# oresat-minusz-end-card.net
KiCad netlist of a schematic drawn in EAGLE
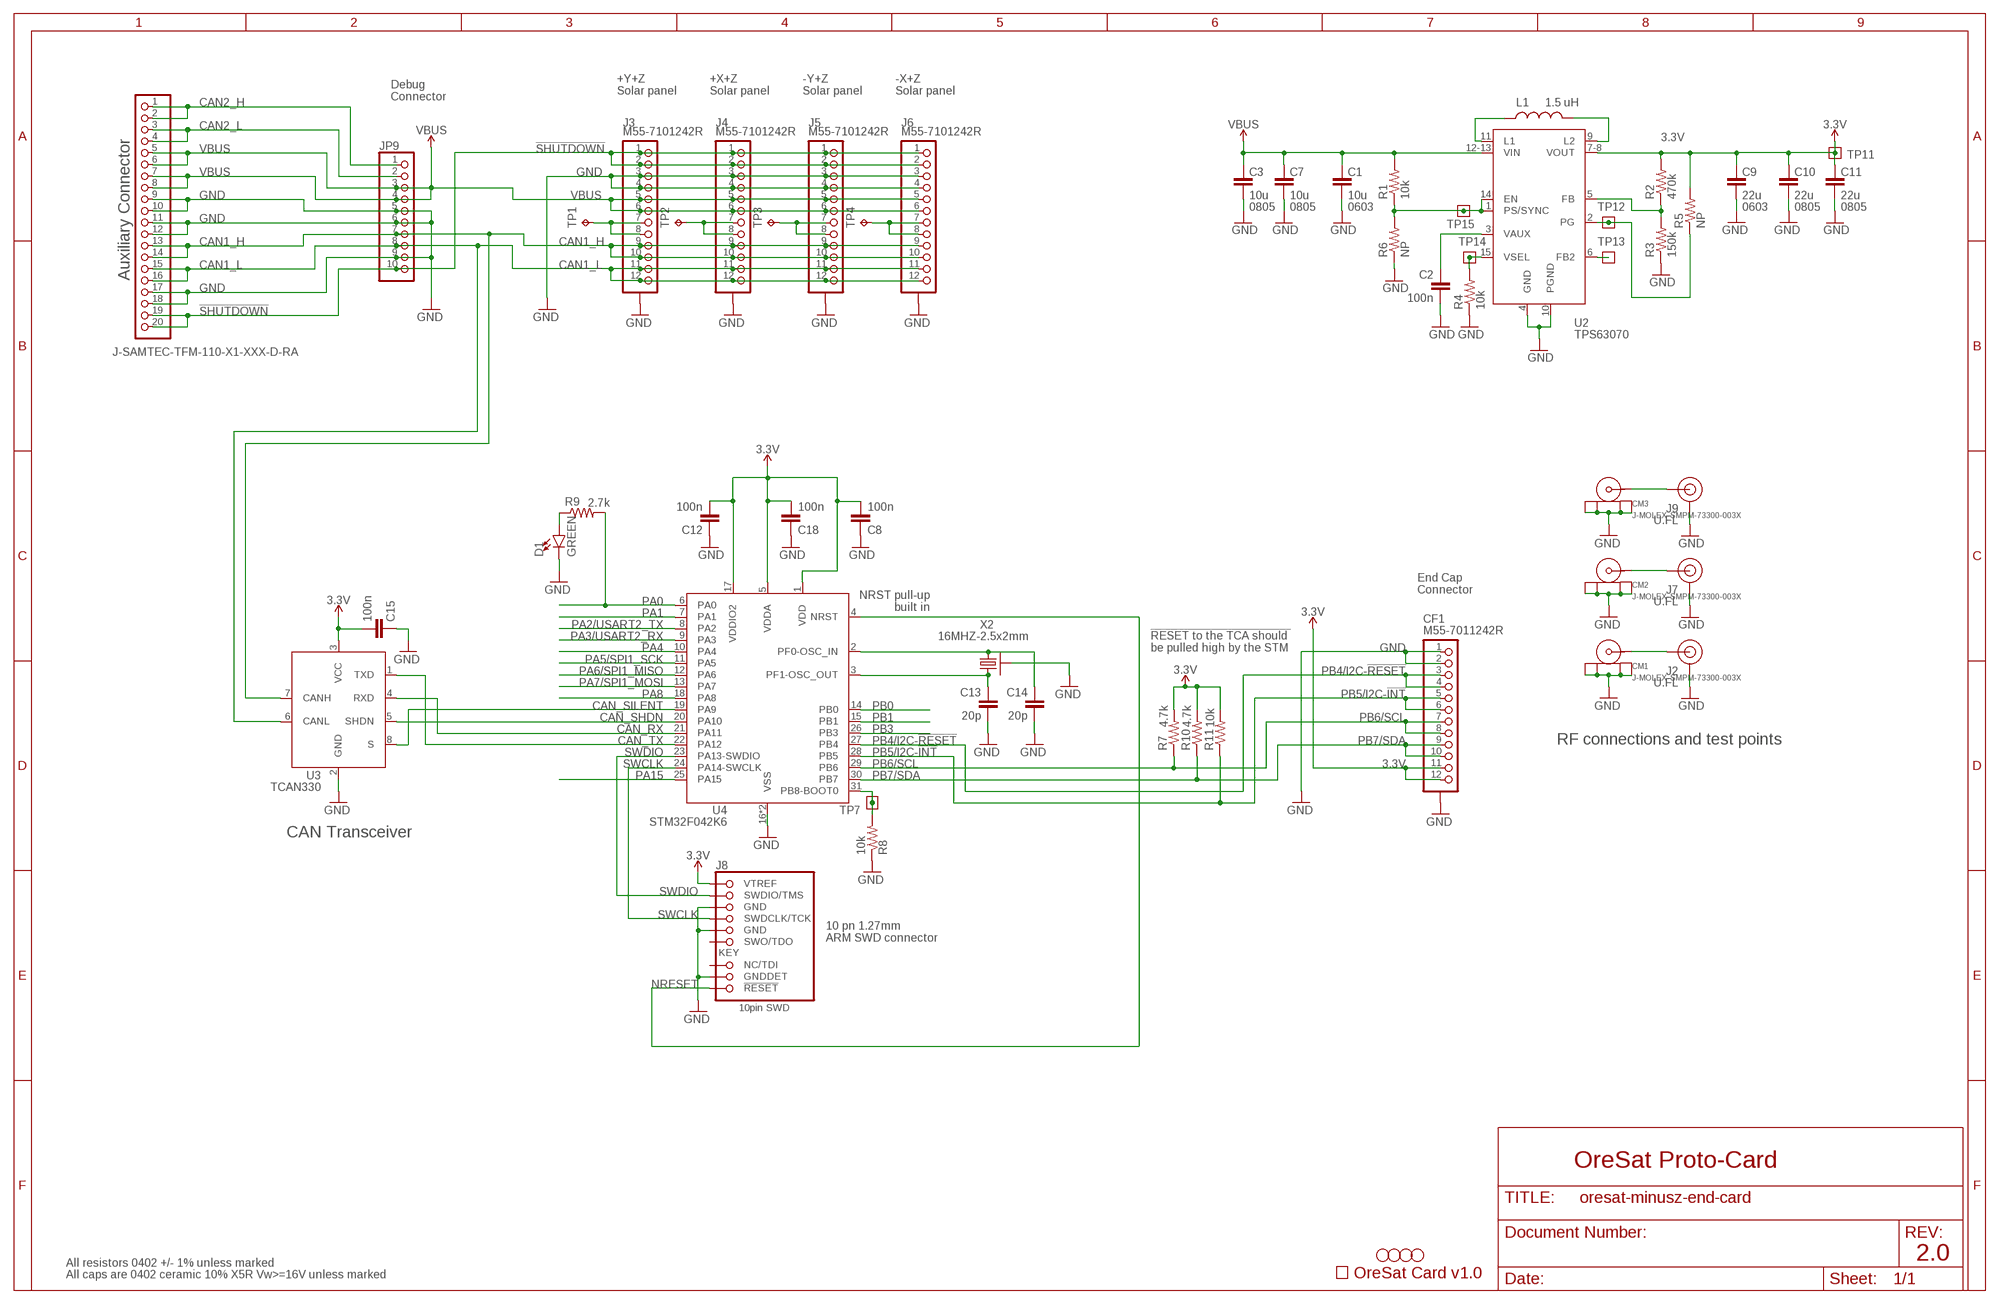
[diagram p0: schematic, sheet 1]

(export (version "E")
  (design (tool "Eeschema 10.0.6"))
  (components
    (comp (ref "C1")
      (value "10u")
      (footprint "eagle-import:.0603-B-NOSILK")
      (fields (field (name "MFR") "Samsung") (field (name "MPN") "CL05B104KO5NNNC"))
      (libsource (lib "eagle-import") (part "C-EU0603-B-NOSILK"))
    )
    (comp (ref "C2")
      (value "100n")
      (footprint "eagle-import:.0402-B-NOSILK")
      (fields (field (name "MFR") "Samsung") (field (name "MPN") "CL05B104KO5NNNC"))
      (libsource (lib "eagle-import") (part "rcl_custom_C-EU0402-B-NOSILK"))
    )
    (comp (ref "C3")
      (value "10u")
      (footprint "eagle-import:.0805-B-NOSILK")
      (libsource (lib "eagle-import") (part "C-EU0805-B-NOSILK"))
    )
    (comp (ref "C7")
      (value "10u")
      (footprint "eagle-import:.0805-B-NOSILK")
      (libsource (lib "eagle-import") (part "C-EU0805-B-NOSILK"))
    )
    (comp (ref "C8")
      (value "100n")
      (footprint "eagle-import:.0402-B-NOSILK")
      (fields (field (name "MFR") "Samsung") (field (name "MPN") "CL05B104KO5NNNC"))
      (libsource (lib "eagle-import") (part "rcl_custom_C-EU0402-B-NOSILK"))
    )
    (comp (ref "C9")
      (value "22u")
      (footprint "eagle-import:.0603-B-NOSILK")
      (fields (field (name "MFR") "Samsung") (field (name "MPN") "CL05B104KO5NNNC"))
      (libsource (lib "eagle-import") (part "C-EU0603-B-NOSILK"))
    )
    (comp (ref "C10")
      (value "22u")
      (footprint "eagle-import:.0805-B-NOSILK")
      (libsource (lib "eagle-import") (part "C-EU0805-B-NOSILK"))
    )
    (comp (ref "C11")
      (value "22u")
      (footprint "eagle-import:.0805-B-NOSILK")
      (libsource (lib "eagle-import") (part "C-EU0805-B-NOSILK"))
    )
    (comp (ref "C12")
      (value "100n")
      (footprint "eagle-import:.0402-B-NOSILK")
      (fields (field (name "MFR") "Samsung") (field (name "MPN") "CL05B104KO5NNNC"))
      (libsource (lib "eagle-import") (part "rcl_custom_C-EU0402-B-NOSILK"))
    )
    (comp (ref "C13")
      (value "20p")
      (footprint "eagle-import:.0402-B-NOSILK")
      (fields (field (name "MFR") "Samsung") (field (name "MPN") "CL05C200JB51PNC"))
      (libsource (lib "eagle-import") (part "rcl_custom_C-EU0402-B-NOSILK"))
    )
    (comp (ref "C14")
      (value "20p")
      (footprint "eagle-import:.0402-B-NOSILK")
      (fields (field (name "MFR") "Samsung") (field (name "MPN") "CL05C200JB51PNC"))
      (libsource (lib "eagle-import") (part "rcl_custom_C-EU0402-B-NOSILK"))
    )
    (comp (ref "C15")
      (value "100n")
      (footprint "eagle-import:.0402-B-NOSILK")
      (fields (field (name "MFR") "Samsung") (field (name "MPN") "CL05B104KO5NNNC"))
      (libsource (lib "eagle-import") (part "rcl_custom_C-EU0402-B-NOSILK"))
    )
    (comp (ref "C18")
      (value "100n")
      (footprint "eagle-import:.0402-B-NOSILK")
      (fields (field (name "MFR") "Samsung") (field (name "MPN") "CL05B104KO5NNNC"))
      (libsource (lib "eagle-import") (part "rcl_custom_C-EU0402-B-NOSILK"))
    )
    (comp (ref "CARD")
      (value "ORESAT-CARD-V0.5")
      (footprint "eagle-import:ORESAT-CARD-V1.0")
      (libsource (lib "eagle-import") (part "ORESAT-CARD-V0.5"))
    )
    (comp (ref "CF1")
      (value "M55-7011242R")
      (footprint "eagle-import:HARWIN-M55-6021242R")
      (libsource (lib "eagle-import") (part "J-HARWIN-M55-6021242R"))
    )
    (comp (ref "CM1")
      (value "J-MOLEX-SMPM-73300-003X")
      (footprint "eagle-import:J-MOLEX-SMPM-073300-003X")
      (libsource (lib "eagle-import") (part "J-MOLEX-SMPM-73300-003X"))
    )
    (comp (ref "CM2")
      (value "J-MOLEX-SMPM-73300-003X")
      (footprint "eagle-import:J-MOLEX-SMPM-073300-003X")
      (libsource (lib "eagle-import") (part "J-MOLEX-SMPM-73300-003X"))
    )
    (comp (ref "CM3")
      (value "J-MOLEX-SMPM-73300-003X")
      (footprint "eagle-import:J-MOLEX-SMPM-073300-003X")
      (libsource (lib "eagle-import") (part "J-MOLEX-SMPM-73300-003X"))
    )
    (comp (ref "D1")
      (value "GREEN")
      (footprint "eagle-import:LED-0603")
      (libsource (lib "eagle-import") (part "LED-GREEN0603"))
    )
    (comp (ref "H1")
      (value "STAND-OFFTIGHT")
      (footprint "eagle-import:STAND-OFF-TIGHT")
      (libsource (lib "eagle-import") (part "STAND-OFFTIGHT"))
    )
    (comp (ref "H2")
      (value "STAND-OFFTIGHT")
      (footprint "eagle-import:STAND-OFF-TIGHT")
      (libsource (lib "eagle-import") (part "STAND-OFFTIGHT"))
    )
    (comp (ref "H3")
      (value "STAND-OFFTIGHT")
      (footprint "eagle-import:STAND-OFF-TIGHT")
      (libsource (lib "eagle-import") (part "STAND-OFFTIGHT"))
    )
    (comp (ref "H4")
      (value "STAND-OFFTIGHT")
      (footprint "eagle-import:STAND-OFF-TIGHT")
      (libsource (lib "eagle-import") (part "STAND-OFFTIGHT"))
    )
    (comp (ref "J1")
      (value "J-SAMTEC-TFM-110-X1-XXX-D-RA")
      (footprint "eagle-import:J-SAMTEC-TFM-110-X1-XXX-D-RA")
      (fields (field (name "MFR") "Samtec") (field (name "MPN") "TFM-110-01-L-D-RA "))
      (libsource (lib "eagle-import") (part "J-SAMTEC-TFM-110-X1-XXX-D-RA"))
    )
    (comp (ref "J2")
      (value "U.FL")
      (footprint "eagle-import:U.FL")
      (libsource (lib "eagle-import") (part "U.FL2PIN"))
    )
    (comp (ref "J3")
      (value "M55-7101242R")
      (footprint "eagle-import:M55-7101242R")
      (libsource (lib "eagle-import") (part "M55-7101242R"))
    )
    (comp (ref "J4")
      (value "M55-7101242R")
      (footprint "eagle-import:M55-7101242R")
      (libsource (lib "eagle-import") (part "M55-7101242R"))
    )
    (comp (ref "J5")
      (value "M55-7101242R")
      (footprint "eagle-import:M55-7101242R")
      (libsource (lib "eagle-import") (part "M55-7101242R"))
    )
    (comp (ref "J6")
      (value "M55-7101242R")
      (footprint "eagle-import:M55-7101242R")
      (libsource (lib "eagle-import") (part "M55-7101242R"))
    )
    (comp (ref "J7")
      (value "U.FL")
      (footprint "eagle-import:U.FL")
      (libsource (lib "eagle-import") (part "U.FL2PIN"))
    )
    (comp (ref "J8")
      (value "FTSH-105-XX-X-DV-K")
      (footprint "eagle-import:CON10_2X5_DUK_FTSH")
      (fields (field (name "MFR") "CNC Tech") (field (name "MPN") "3220-10-0100-00"))
      (libsource (lib "eagle-import") (part "FTSH-105-XX-X-DV-K"))
    )
    (comp (ref "J9")
      (value "U.FL")
      (footprint "eagle-import:U.FL")
      (libsource (lib "eagle-import") (part "U.FL2PIN"))
    )
    (comp (ref "JP9")
      (value "PINHD-1X10")
      (footprint "eagle-import:1X10")
      (libsource (lib "eagle-import") (part "PINHD-1X10"))
    )
    (comp (ref "L1")
      (value "1.5 uH")
      (footprint "eagle-import:L-COILCRAFT-XFL4020")
      (fields (field (name "MFR") "Coilcraft") (field (name "MPN") "XFL4020-152ME"))
      (libsource (lib "eagle-import") (part "L-COILCRAFT-XFL4020"))
    )
    (comp (ref "R1")
      (value "10k")
      (footprint "eagle-import:.0402-B-NOSILK")
      (fields (field (name "MFR") "Samsung") (field (name "MPN") "RC1005F6653CS"))
      (libsource (lib "eagle-import") (part "R-US_0402-B-NOSILK"))
    )
    (comp (ref "R2")
      (value "470k")
      (footprint "eagle-import:.0402-B-NOSILK")
      (fields (field (name "MFR") "Samsung") (field (name "MPN") "RC1005F6653CS"))
      (libsource (lib "eagle-import") (part "R-US_0402-B-NOSILK"))
    )
    (comp (ref "R3")
      (value "150k")
      (footprint "eagle-import:.0402-B-NOSILK")
      (fields (field (name "MFR") "Samsung") (field (name "MPN") "RC1005F6653CS"))
      (libsource (lib "eagle-import") (part "R-US_0402-B-NOSILK"))
    )
    (comp (ref "R4")
      (value "10k")
      (footprint "eagle-import:.0402-B-NOSILK")
      (fields (field (name "MFR") "Samsung") (field (name "MPN") "RC1005F6653CS"))
      (libsource (lib "eagle-import") (part "R-US_0402-B-NOSILK"))
    )
    (comp (ref "R5")
      (value "NP")
      (footprint "eagle-import:.0402-B-NOSILK")
      (fields (field (name "MFR") "Samsung") (field (name "MPN") "RC1005F6653CS"))
      (libsource (lib "eagle-import") (part "R-US_0402-B-NOSILK"))
    )
    (comp (ref "R6")
      (value "NP")
      (footprint "eagle-import:.0402-B-NOSILK")
      (fields (field (name "MFR") "Samsung") (field (name "MPN") "RC1005F6653CS"))
      (libsource (lib "eagle-import") (part "R-US_0402-B-NOSILK"))
    )
    (comp (ref "R7")
      (value "4.7k")
      (footprint "eagle-import:.0402-B-NOSILK")
      (fields (field (name "MFR") "Samsung") (field (name "MPN") "RC1005F6653CS"))
      (libsource (lib "eagle-import") (part "R-US_0402-B-NOSILK"))
    )
    (comp (ref "R8")
      (value "10k")
      (footprint "eagle-import:.0402-B-NOSILK")
      (fields (field (name "MFR") "Samsung") (field (name "MPN") "RC1005F6653CS"))
      (libsource (lib "eagle-import") (part "R-US_0402-B-NOSILK"))
    )
    (comp (ref "R9")
      (value "2.7k")
      (footprint "eagle-import:.0402-B-NOSILK")
      (fields (field (name "MFR") "Samsung") (field (name "MPN") "RC1005F6653CS"))
      (libsource (lib "eagle-import") (part "R-US_0402-B-NOSILK"))
    )
    (comp (ref "R10")
      (value "4.7k")
      (footprint "eagle-import:.0402-B-NOSILK")
      (fields (field (name "MFR") "Samsung") (field (name "MPN") "RC1005F6653CS"))
      (libsource (lib "eagle-import") (part "R-US_0402-B-NOSILK"))
    )
    (comp (ref "R11")
      (value "10k")
      (footprint "eagle-import:.0402-B-NOSILK")
      (fields (field (name "MFR") "Samsung") (field (name "MPN") "RC1005F6653CS"))
      (libsource (lib "eagle-import") (part "R-US_0402-B-NOSILK"))
    )
    (comp (ref "TP1")
      (value "TPPAD1-13")
      (footprint "eagle-import:P1-13")
      (libsource (lib "eagle-import") (part "TPPAD1-13"))
    )
    (comp (ref "TP2")
      (value "TPPAD1-13")
      (footprint "eagle-import:P1-13")
      (libsource (lib "eagle-import") (part "TPPAD1-13"))
    )
    (comp (ref "TP3")
      (value "TPPAD1-13")
      (footprint "eagle-import:P1-13")
      (libsource (lib "eagle-import") (part "TPPAD1-13"))
    )
    (comp (ref "TP4")
      (value "TPPAD1-13")
      (footprint "eagle-import:P1-13")
      (libsource (lib "eagle-import") (part "TPPAD1-13"))
    )
    (comp (ref "TP7")
      (value "TEST-POINT")
      (footprint "eagle-import:2MM-TEST-POINT")
      (libsource (lib "eagle-import") (part "TEST-POINT"))
    )
    (comp (ref "TP11")
      (value "TEST-POINT")
      (footprint "eagle-import:2MM-TEST-POINT")
      (libsource (lib "eagle-import") (part "TEST-POINT"))
    )
    (comp (ref "TP12")
      (value "TEST-POINT")
      (footprint "eagle-import:2MM-TEST-POINT")
      (libsource (lib "eagle-import") (part "TEST-POINT"))
    )
    (comp (ref "TP13")
      (value "TEST-POINT")
      (footprint "eagle-import:2MM-TEST-POINT")
      (libsource (lib "eagle-import") (part "TEST-POINT"))
    )
    (comp (ref "TP14")
      (value "TEST-POINT")
      (footprint "eagle-import:2MM-TEST-POINT")
      (libsource (lib "eagle-import") (part "TEST-POINT"))
    )
    (comp (ref "TP15")
      (value "TEST-POINT")
      (footprint "eagle-import:2MM-TEST-POINT")
      (libsource (lib "eagle-import") (part "TEST-POINT"))
    )
    (comp (ref "U2")
      (value "TPS63070")
      (footprint "eagle-import:TPS63070X")
      (fields (field (name "MFR") "TI"))
      (libsource (lib "eagle-import") (part "TPS63070X"))
    )
    (comp (ref "U3")
      (value "TCAN330")
      (footprint "eagle-import:SOT23-8_TI-DCN")
      (fields (field (name "MFR") "Texas Instruments") (field (name "MPN") "TCAN330GDCNT"))
      (libsource (lib "eagle-import") (part "TCAN330"))
    )
    (comp (ref "U4")
      (value "STM32F042K6")
      (footprint "eagle-import:QFP32-7X7")
      (fields (field (name "MFR") "STMicroelectronics") (field (name "MPN") "STM32F042K6T7"))
      (libsource (lib "eagle-import") (part "STM32F042K6"))
    )
    (comp (ref "X2")
      (value "16MHZ-2.5x2mm")
      (footprint "eagle-import:CRYSTAL_2.5X2")
      (fields (field (name "MFR") "ECS Inc.") (field (name "MPN") "ECS-160-10-36Q-ES-TR"))
      (libsource (lib "eagle-import") (part "CRYSTAL-WITH-GND"))
    )
  )
  (nets
    (net (code "1") (name "/CAN1_H") (class "Default")
      (node (ref "J1") (pin "13") (pinfunction "13_13") (pintype "passive"))
      (node (ref "J1") (pin "14") (pinfunction "14_14") (pintype "passive"))
      (node (ref "J3") (pin "10") (pinfunction "10_10") (pintype "passive"))
      (node (ref "J3") (pin "9") (pinfunction "9_9") (pintype "passive"))
      (node (ref "J4") (pin "10") (pinfunction "10_10") (pintype "passive"))
      (node (ref "J4") (pin "9") (pinfunction "9_9") (pintype "passive"))
      (node (ref "J5") (pin "10") (pinfunction "10_10") (pintype "passive"))
      (node (ref "J5") (pin "9") (pinfunction "9_9") (pintype "passive"))
      (node (ref "J6") (pin "10") (pinfunction "10_10") (pintype "passive"))
      (node (ref "J6") (pin "9") (pinfunction "9_9") (pintype "passive"))
      (node (ref "JP9") (pin "7") (pinfunction "7_7") (pintype "passive"))
      (node (ref "U3") (pin "7") (pinfunction "CANH_7") (pintype "bidirectional"))
    )
    (net (code "2") (name "/CAN1_L") (class "Default")
      (node (ref "J1") (pin "15") (pinfunction "15_15") (pintype "passive"))
      (node (ref "J1") (pin "16") (pinfunction "16_16") (pintype "passive"))
      (node (ref "J3") (pin "11") (pinfunction "11_11") (pintype "passive"))
      (node (ref "J3") (pin "12") (pinfunction "12_12") (pintype "passive"))
      (node (ref "J4") (pin "11") (pinfunction "11_11") (pintype "passive"))
      (node (ref "J4") (pin "12") (pinfunction "12_12") (pintype "passive"))
      (node (ref "J5") (pin "11") (pinfunction "11_11") (pintype "passive"))
      (node (ref "J5") (pin "12") (pinfunction "12_12") (pintype "passive"))
      (node (ref "J6") (pin "11") (pinfunction "11_11") (pintype "passive"))
      (node (ref "J6") (pin "12") (pinfunction "12_12") (pintype "passive"))
      (node (ref "JP9") (pin "8") (pinfunction "8_8") (pintype "passive"))
      (node (ref "U3") (pin "6") (pinfunction "CANL_6") (pintype "bidirectional"))
    )
    (net (code "3") (name "/CAN2_H") (class "Default")
      (node (ref "J1") (pin "1") (pinfunction "1_1") (pintype "passive"))
      (node (ref "J1") (pin "2") (pinfunction "2_2") (pintype "passive"))
      (node (ref "JP9") (pin "1") (pinfunction "1_1") (pintype "passive"))
    )
    (net (code "4") (name "/CAN2_L") (class "Default")
      (node (ref "J1") (pin "3") (pinfunction "3_3") (pintype "passive"))
      (node (ref "J1") (pin "4") (pinfunction "4_4") (pintype "passive"))
      (node (ref "JP9") (pin "2") (pinfunction "2_2") (pintype "passive"))
    )
    (net (code "5") (name "/CAN_RX") (class "Default")
      (node (ref "U3") (pin "4") (pinfunction "RXD_4") (pintype "output"))
      (node (ref "U4") (pin "21") (pinfunction "PA11_21") (pintype "bidirectional"))
    )
    (net (code "6") (name "/CAN_SHDN") (class "Default")
      (node (ref "U3") (pin "5") (pinfunction "SHDN_5") (pintype "input"))
      (node (ref "U4") (pin "20") (pinfunction "PA10_20") (pintype "bidirectional"))
    )
    (net (code "7") (name "/CAN_SILENT") (class "Default")
      (node (ref "U3") (pin "8") (pinfunction "S_8") (pintype "input"))
      (node (ref "U4") (pin "19") (pinfunction "PA9_19") (pintype "bidirectional"))
    )
    (net (code "8") (name "/CAN_TX") (class "Default")
      (node (ref "U3") (pin "1") (pinfunction "TXD_1") (pintype "input"))
      (node (ref "U4") (pin "22") (pinfunction "PA12_22") (pintype "bidirectional"))
    )
    (net (code "9") (name "/NRESET") (class "Default")
      (node (ref "J8") (pin "10") (pinfunction "~{RESET}_10") (pintype "passive"))
      (node (ref "U4") (pin "4") (pinfunction "NRST_4") (pintype "bidirectional"))
    )
    (net (code "10") (name "/PA0") (class "Default")
      (node (ref "R9") (pin "2") (pinfunction "2_2") (pintype "passive"))
      (node (ref "U4") (pin "6") (pinfunction "PA0_6") (pintype "bidirectional"))
    )
    (net (code "11") (name "/PA1") (class "Default")
      (node (ref "U4") (pin "7") (pinfunction "PA1_7") (pintype "bidirectional"))
    )
    (net (code "12") (name "/PA2{slash}USART2_TX") (class "Default")
      (node (ref "U4") (pin "8") (pinfunction "PA2_8") (pintype "bidirectional"))
    )
    (net (code "13") (name "/PA3{slash}USART2_RX") (class "Default")
      (node (ref "U4") (pin "9") (pinfunction "PA3_9") (pintype "bidirectional"))
    )
    (net (code "14") (name "/PA4") (class "Default")
      (node (ref "U4") (pin "10") (pinfunction "PA4_10") (pintype "bidirectional"))
    )
    (net (code "15") (name "/PA5{slash}SPI1_SCK") (class "Default")
      (node (ref "U4") (pin "11") (pinfunction "PA5_11") (pintype "bidirectional"))
    )
    (net (code "16") (name "/PA6{slash}SPI1_MISO") (class "Default")
      (node (ref "U4") (pin "12") (pinfunction "PA6_12") (pintype "bidirectional"))
    )
    (net (code "17") (name "/PA7{slash}SPI1_MOSI") (class "Default")
      (node (ref "U4") (pin "13") (pinfunction "PA7_13") (pintype "bidirectional"))
    )
    (net (code "18") (name "/PA8") (class "Default")
      (node (ref "U4") (pin "18") (pinfunction "PA8_18") (pintype "bidirectional"))
    )
    (net (code "19") (name "/PA15") (class "Default")
      (node (ref "U4") (pin "25") (pinfunction "PA15_25") (pintype "bidirectional"))
    )
    (net (code "20") (name "/PB0") (class "Default")
      (node (ref "U4") (pin "14") (pinfunction "PB0_14") (pintype "bidirectional"))
    )
    (net (code "21") (name "/PB1") (class "Default")
      (node (ref "U4") (pin "15") (pinfunction "PB1_15") (pintype "bidirectional"))
    )
    (net (code "22") (name "/PB3") (class "Default")
      (node (ref "U4") (pin "26") (pinfunction "PB3_26") (pintype "bidirectional"))
    )
    (net (code "23") (name "/PB4{slash}I2C-~{RESET}") (class "Default")
      (node (ref "CF1") (pin "3") (pinfunction "3_3") (pintype "passive"))
      (node (ref "CF1") (pin "4") (pinfunction "4_4") (pintype "passive"))
      (node (ref "U4") (pin "27") (pinfunction "PB4_27") (pintype "bidirectional"))
    )
    (net (code "24") (name "/PB5{slash}I2C-~{INT}") (class "Default")
      (node (ref "CF1") (pin "5") (pinfunction "5_5") (pintype "passive"))
      (node (ref "CF1") (pin "6") (pinfunction "6_6") (pintype "passive"))
      (node (ref "R11") (pin "1") (pinfunction "1_1") (pintype "passive"))
      (node (ref "U4") (pin "28") (pinfunction "PB5_28") (pintype "bidirectional"))
    )
    (net (code "25") (name "/PB6{slash}SCL") (class "Default")
      (node (ref "CF1") (pin "7") (pinfunction "7_7") (pintype "passive"))
      (node (ref "CF1") (pin "8") (pinfunction "8_8") (pintype "passive"))
      (node (ref "R7") (pin "1") (pinfunction "1_1") (pintype "passive"))
      (node (ref "U4") (pin "29") (pinfunction "PB6_29") (pintype "bidirectional"))
    )
    (net (code "26") (name "/PB7{slash}SDA") (class "Default")
      (node (ref "CF1") (pin "10") (pinfunction "10_10") (pintype "passive"))
      (node (ref "CF1") (pin "9") (pinfunction "9_9") (pintype "passive"))
      (node (ref "R10") (pin "1") (pinfunction "1_1") (pintype "passive"))
      (node (ref "U4") (pin "30") (pinfunction "PB7_30") (pintype "bidirectional"))
    )
    (net (code "27") (name "/SWCLK") (class "Default")
      (node (ref "J8") (pin "4") (pinfunction "SWDCLK/TCK_4") (pintype "passive"))
      (node (ref "U4") (pin "24") (pinfunction "PA14-SWCLK_24") (pintype "bidirectional"))
    )
    (net (code "28") (name "/SWDIO") (class "Default")
      (node (ref "J8") (pin "2") (pinfunction "SWDIO/TMS_2") (pintype "passive"))
      (node (ref "U4") (pin "23") (pinfunction "PA13-SWDIO_23") (pintype "bidirectional"))
    )
    (net (code "29") (name "/~{SHUTDOWN}") (class "Default")
      (node (ref "J1") (pin "19") (pinfunction "19_19") (pintype "passive"))
      (node (ref "J1") (pin "20") (pinfunction "20_20") (pintype "passive"))
      (node (ref "J3") (pin "1") (pinfunction "1_1") (pintype "passive"))
      (node (ref "J3") (pin "2") (pinfunction "2_2") (pintype "passive"))
      (node (ref "J4") (pin "1") (pinfunction "1_1") (pintype "passive"))
      (node (ref "J4") (pin "2") (pinfunction "2_2") (pintype "passive"))
      (node (ref "J5") (pin "1") (pinfunction "1_1") (pintype "passive"))
      (node (ref "J5") (pin "2") (pinfunction "2_2") (pintype "passive"))
      (node (ref "J6") (pin "1") (pinfunction "1_1") (pintype "passive"))
      (node (ref "J6") (pin "2") (pinfunction "2_2") (pintype "passive"))
      (node (ref "JP9") (pin "10") (pinfunction "10_10") (pintype "passive"))
    )
    (net (code "30") (name "3.3V") (class "Default")
      (node (ref "C10") (pin "1") (pinfunction "1_1") (pintype "passive"))
      (node (ref "C11") (pin "1") (pinfunction "1_1") (pintype "passive"))
      (node (ref "C12") (pin "2") (pinfunction "2_2") (pintype "passive"))
      (node (ref "C15") (pin "2") (pinfunction "2_2") (pintype "passive"))
      (node (ref "C18") (pin "2") (pinfunction "2_2") (pintype "passive"))
      (node (ref "C8") (pin "2") (pinfunction "2_2") (pintype "passive"))
      (node (ref "C9") (pin "1") (pinfunction "1_1") (pintype "passive"))
      (node (ref "CF1") (pin "11") (pinfunction "11_11") (pintype "passive"))
      (node (ref "CF1") (pin "12") (pinfunction "12_12") (pintype "passive"))
      (node (ref "J8") (pin "1") (pinfunction "VTREF_1") (pintype "passive"))
      (node (ref "R10") (pin "2") (pinfunction "2_2") (pintype "passive"))
      (node (ref "R11") (pin "2") (pinfunction "2_2") (pintype "passive"))
      (node (ref "R2") (pin "2") (pinfunction "2_2") (pintype "passive"))
      (node (ref "R5") (pin "2") (pinfunction "2_2") (pintype "passive"))
      (node (ref "R7") (pin "2") (pinfunction "2_2") (pintype "passive"))
      (node (ref "TP11") (pin "1") (pinfunction "1_1") (pintype "passive"))
      (node (ref "U2") (pin "7-8") (pinfunction "VOUT_7-8") (pintype "power_in"))
      (node (ref "U3") (pin "3") (pinfunction "VCC_3") (pintype "power_in"))
      (node (ref "U4") (pin "1") (pinfunction "VDD_1") (pintype "power_in"))
      (node (ref "U4") (pin "17") (pinfunction "VDDIO2_17") (pintype "power_in"))
      (node (ref "U4") (pin "5") (pinfunction "VDDA_5") (pintype "power_in"))
    )
    (net (code "31") (name "GND") (class "Default")
      (node (ref "C1") (pin "2") (pinfunction "2_2") (pintype "passive"))
      (node (ref "C10") (pin "2") (pinfunction "2_2") (pintype "passive"))
      (node (ref "C11") (pin "2") (pinfunction "2_2") (pintype "passive"))
      (node (ref "C12") (pin "1") (pinfunction "1_1") (pintype "passive"))
      (node (ref "C13") (pin "2") (pinfunction "2_2") (pintype "passive"))
      (node (ref "C14") (pin "2") (pinfunction "2_2") (pintype "passive"))
      (node (ref "C15") (pin "1") (pinfunction "1_1") (pintype "passive"))
      (node (ref "C18") (pin "1") (pinfunction "1_1") (pintype "passive"))
      (node (ref "C2") (pin "2") (pinfunction "2_2") (pintype "passive"))
      (node (ref "C3") (pin "2") (pinfunction "2_2") (pintype "passive"))
      (node (ref "C7") (pin "2") (pinfunction "2_2") (pintype "passive"))
      (node (ref "C8") (pin "1") (pinfunction "1_1") (pintype "passive"))
      (node (ref "C9") (pin "2") (pinfunction "2_2") (pintype "passive"))
      (node (ref "CF1") (pin "1") (pinfunction "1_1") (pintype "passive"))
      (node (ref "CF1") (pin "2") (pinfunction "2_2") (pintype "passive"))
      (node (ref "CF1") (pin "P$1") (pinfunction "SHIELDS_P$1") (pintype "passive"))
      (node (ref "CF1") (pin "P$2") (pinfunction "SHIELDS_P$2") (pintype "passive"))
      (node (ref "CF1") (pin "P$3") (pinfunction "SHIELDS_P$3") (pintype "passive"))
      (node (ref "CF1") (pin "P$4") (pinfunction "SHIELDS_P$4") (pintype "passive"))
      (node (ref "CM1") (pin "P$1") (pinfunction "SHIELD3_P$1") (pintype "passive"))
      (node (ref "CM1") (pin "P$2") (pinfunction "SHIELD2_P$2") (pintype "passive"))
      (node (ref "CM1") (pin "P$3") (pinfunction "SHIELD1_P$3") (pintype "passive"))
      (node (ref "CM1") (pin "P$4") (pinfunction "SHIELD_P$4") (pintype "passive"))
      (node (ref "CM2") (pin "P$1") (pinfunction "SHIELD3_P$1") (pintype "passive"))
      (node (ref "CM2") (pin "P$2") (pinfunction "SHIELD2_P$2") (pintype "passive"))
      (node (ref "CM2") (pin "P$3") (pinfunction "SHIELD1_P$3") (pintype "passive"))
      (node (ref "CM2") (pin "P$4") (pinfunction "SHIELD_P$4") (pintype "passive"))
      (node (ref "CM3") (pin "P$1") (pinfunction "SHIELD3_P$1") (pintype "passive"))
      (node (ref "CM3") (pin "P$2") (pinfunction "SHIELD2_P$2") (pintype "passive"))
      (node (ref "CM3") (pin "P$3") (pinfunction "SHIELD1_P$3") (pintype "passive"))
      (node (ref "CM3") (pin "P$4") (pinfunction "SHIELD_P$4") (pintype "passive"))
      (node (ref "D1") (pin "C") (pinfunction "C_C") (pintype "passive"))
      (node (ref "J1") (pin "10") (pinfunction "10_10") (pintype "passive"))
      (node (ref "J1") (pin "11") (pinfunction "11_11") (pintype "passive"))
      (node (ref "J1") (pin "12") (pinfunction "12_12") (pintype "passive"))
      (node (ref "J1") (pin "17") (pinfunction "17_17") (pintype "passive"))
      (node (ref "J1") (pin "18") (pinfunction "18_18") (pintype "passive"))
      (node (ref "J1") (pin "9") (pinfunction "9_9") (pintype "passive"))
      (node (ref "J2") (pin "1") (pinfunction "GND_1") (pintype "bidirectional"))
      (node (ref "J2") (pin "2") (pinfunction "GND_2") (pintype "bidirectional"))
      (node (ref "J3") (pin "3") (pinfunction "3_3") (pintype "passive"))
      (node (ref "J3") (pin "4") (pinfunction "4_4") (pintype "passive"))
      (node (ref "J3") (pin "P$1") (pinfunction "SHIELD_P$1") (pintype "passive"))
      (node (ref "J3") (pin "P$2") (pinfunction "SHIELD_P$2") (pintype "passive"))
      (node (ref "J3") (pin "P$3") (pinfunction "SHIELD_P$3") (pintype "passive"))
      (node (ref "J3") (pin "P$4") (pinfunction "SHIELD_P$4") (pintype "passive"))
      (node (ref "J4") (pin "3") (pinfunction "3_3") (pintype "passive"))
      (node (ref "J4") (pin "4") (pinfunction "4_4") (pintype "passive"))
      (node (ref "J4") (pin "P$1") (pinfunction "SHIELD_P$1") (pintype "passive"))
      (node (ref "J4") (pin "P$2") (pinfunction "SHIELD_P$2") (pintype "passive"))
      (node (ref "J4") (pin "P$3") (pinfunction "SHIELD_P$3") (pintype "passive"))
      (node (ref "J4") (pin "P$4") (pinfunction "SHIELD_P$4") (pintype "passive"))
      (node (ref "J5") (pin "3") (pinfunction "3_3") (pintype "passive"))
      (node (ref "J5") (pin "4") (pinfunction "4_4") (pintype "passive"))
      (node (ref "J5") (pin "P$1") (pinfunction "SHIELD_P$1") (pintype "passive"))
      (node (ref "J5") (pin "P$2") (pinfunction "SHIELD_P$2") (pintype "passive"))
      (node (ref "J5") (pin "P$3") (pinfunction "SHIELD_P$3") (pintype "passive"))
      (node (ref "J5") (pin "P$4") (pinfunction "SHIELD_P$4") (pintype "passive"))
      (node (ref "J6") (pin "3") (pinfunction "3_3") (pintype "passive"))
      (node (ref "J6") (pin "4") (pinfunction "4_4") (pintype "passive"))
      (node (ref "J6") (pin "P$1") (pinfunction "SHIELD_P$1") (pintype "passive"))
      (node (ref "J6") (pin "P$2") (pinfunction "SHIELD_P$2") (pintype "passive"))
      (node (ref "J6") (pin "P$3") (pinfunction "SHIELD_P$3") (pintype "passive"))
      (node (ref "J6") (pin "P$4") (pinfunction "SHIELD_P$4") (pintype "passive"))
      (node (ref "J7") (pin "1") (pinfunction "GND_1") (pintype "bidirectional"))
      (node (ref "J7") (pin "2") (pinfunction "GND_2") (pintype "bidirectional"))
      (node (ref "J8") (pin "3") (pinfunction "GND_3") (pintype "passive"))
      (node (ref "J8") (pin "5") (pinfunction "GND_5") (pintype "passive"))
      (node (ref "J8") (pin "9") (pinfunction "GNDDET_9") (pintype "passive"))
      (node (ref "J9") (pin "1") (pinfunction "GND_1") (pintype "bidirectional"))
      (node (ref "J9") (pin "2") (pinfunction "GND_2") (pintype "bidirectional"))
      (node (ref "JP9") (pin "5") (pinfunction "5_5") (pintype "passive"))
      (node (ref "JP9") (pin "6") (pinfunction "6_6") (pintype "passive"))
      (node (ref "JP9") (pin "9") (pinfunction "9_9") (pintype "passive"))
      (node (ref "R3") (pin "1") (pinfunction "1_1") (pintype "passive"))
      (node (ref "R4") (pin "1") (pinfunction "1_1") (pintype "passive"))
      (node (ref "R6") (pin "1") (pinfunction "1_1") (pintype "passive"))
      (node (ref "R8") (pin "1") (pinfunction "1_1") (pintype "passive"))
      (node (ref "U2") (pin "10") (pinfunction "PGND_10") (pintype "power_in"))
      (node (ref "U2") (pin "4") (pinfunction "GND_4") (pintype "power_in"))
      (node (ref "U3") (pin "2") (pinfunction "GND_2") (pintype "power_in"))
      (node (ref "U4") (pin "16") (pinfunction "VSS_16") (pintype "power_in"))
      (node (ref "U4") (pin "32") (pinfunction "VSS_32") (pintype "power_in"))
      (node (ref "X2") (pin "2") (pinfunction "SHIELD_2") (pintype "power_in"))
      (node (ref "X2") (pin "4") (pinfunction "SHIELD_4") (pintype "power_in"))
    )
    (net (code "32") (name "Net-(CM1-CENTER)") (class "Default")
      (node (ref "CM1") (pin "RF") (pinfunction "CENTER_RF") (pintype "passive"))
      (node (ref "J2") (pin "FEED") (pinfunction "SIGNAL_FEED") (pintype "bidirectional"))
    )
    (net (code "33") (name "Net-(CM2-CENTER)") (class "Default")
      (node (ref "CM2") (pin "RF") (pinfunction "CENTER_RF") (pintype "passive"))
      (node (ref "J7") (pin "FEED") (pinfunction "SIGNAL_FEED") (pintype "bidirectional"))
    )
    (net (code "34") (name "Net-(CM3-CENTER)") (class "Default")
      (node (ref "CM3") (pin "RF") (pinfunction "CENTER_RF") (pintype "passive"))
      (node (ref "J9") (pin "FEED") (pinfunction "SIGNAL_FEED") (pintype "bidirectional"))
    )
    (net (code "35") (name "Net-(D1-PadA)") (class "Default")
      (node (ref "D1") (pin "A") (pinfunction "A_A") (pintype "passive"))
      (node (ref "R9") (pin "1") (pinfunction "1_1") (pintype "passive"))
    )
    (net (code "36") (name "Net-(J3-Pad7)") (class "Default")
      (node (ref "J3") (pin "7") (pinfunction "7_7") (pintype "passive"))
      (node (ref "J3") (pin "8") (pinfunction "8_8") (pintype "passive"))
      (node (ref "TP1") (pin "TP") (pinfunction "TP_TP") (pintype "input"))
    )
    (net (code "37") (name "Net-(J4-Pad7)") (class "Default")
      (node (ref "J4") (pin "7") (pinfunction "7_7") (pintype "passive"))
      (node (ref "J4") (pin "8") (pinfunction "8_8") (pintype "passive"))
      (node (ref "TP2") (pin "TP") (pinfunction "TP_TP") (pintype "input"))
    )
    (net (code "38") (name "Net-(J5-Pad7)") (class "Default")
      (node (ref "J5") (pin "7") (pinfunction "7_7") (pintype "passive"))
      (node (ref "J5") (pin "8") (pinfunction "8_8") (pintype "passive"))
      (node (ref "TP3") (pin "TP") (pinfunction "TP_TP") (pintype "input"))
    )
    (net (code "39") (name "Net-(J6-Pad7)") (class "Default")
      (node (ref "J6") (pin "7") (pinfunction "7_7") (pintype "passive"))
      (node (ref "J6") (pin "8") (pinfunction "8_8") (pintype "passive"))
      (node (ref "TP4") (pin "TP") (pinfunction "TP_TP") (pintype "input"))
    )
    (net (code "40") (name "Net-(U2-EN)") (class "Default")
      (node (ref "R1") (pin "1") (pinfunction "1_1") (pintype "passive"))
      (node (ref "R6") (pin "2") (pinfunction "2_2") (pintype "passive"))
      (node (ref "TP15") (pin "1") (pinfunction "1_1") (pintype "passive"))
      (node (ref "U2") (pin "1") (pinfunction "PS/SYNC_1") (pintype "input"))
      (node (ref "U2") (pin "14") (pinfunction "EN_14") (pintype "input"))
    )
    (net (code "41") (name "Net-(U2-FB)") (class "Default")
      (node (ref "R2") (pin "1") (pinfunction "1_1") (pintype "passive"))
      (node (ref "R3") (pin "2") (pinfunction "2_2") (pintype "passive"))
      (node (ref "U2") (pin "5") (pinfunction "FB_5") (pintype "passive"))
    )
    (net (code "42") (name "Net-(U2-FB2)") (class "Default")
      (node (ref "TP13") (pin "1") (pinfunction "1_1") (pintype "passive"))
      (node (ref "U2") (pin "6") (pinfunction "FB2_6") (pintype "passive"))
    )
    (net (code "43") (name "Net-(U2-L1)") (class "Default")
      (node (ref "L1") (pin "1") (pinfunction "1_1") (pintype "passive"))
      (node (ref "U2") (pin "11") (pinfunction "L1_11") (pintype "passive"))
    )
    (net (code "44") (name "Net-(U2-L2)") (class "Default")
      (node (ref "L1") (pin "2") (pinfunction "2_2") (pintype "passive"))
      (node (ref "U2") (pin "9") (pinfunction "L2_9") (pintype "passive"))
    )
    (net (code "45") (name "Net-(U2-PG)") (class "Default")
      (node (ref "R5") (pin "1") (pinfunction "1_1") (pintype "passive"))
      (node (ref "TP12") (pin "1") (pinfunction "1_1") (pintype "passive"))
      (node (ref "U2") (pin "2") (pinfunction "PG_2") (pintype "open_collector"))
    )
    (net (code "46") (name "Net-(U2-VAUX)") (class "Default")
      (node (ref "C2") (pin "1") (pinfunction "1_1") (pintype "passive"))
      (node (ref "U2") (pin "3") (pinfunction "VAUX_3") (pintype "output"))
    )
    (net (code "47") (name "Net-(U2-VSEL)") (class "Default")
      (node (ref "R4") (pin "2") (pinfunction "2_2") (pintype "passive"))
      (node (ref "TP14") (pin "1") (pinfunction "1_1") (pintype "passive"))
      (node (ref "U2") (pin "15") (pinfunction "VSEL_15") (pintype "input"))
    )
    (net (code "48") (name "Net-(U4-PB8-BOOT0)") (class "Default")
      (node (ref "R8") (pin "2") (pinfunction "2_2") (pintype "passive"))
      (node (ref "TP7") (pin "1") (pinfunction "1_1") (pintype "passive"))
      (node (ref "U4") (pin "31") (pinfunction "PB8-BOOT0_31") (pintype "bidirectional"))
    )
    (net (code "49") (name "Net-(U4-PF0-OSC_IN)") (class "Default")
      (node (ref "C14") (pin "1") (pinfunction "1_1") (pintype "passive"))
      (node (ref "U4") (pin "2") (pinfunction "PF0-OSC_IN_2") (pintype "bidirectional"))
      (node (ref "X2") (pin "1") (pinfunction "1_1") (pintype "passive"))
    )
    (net (code "50") (name "Net-(U4-PF1-OSC_OUT)") (class "Default")
      (node (ref "C13") (pin "1") (pinfunction "1_1") (pintype "passive"))
      (node (ref "U4") (pin "3") (pinfunction "PF1-OSC_OUT_3") (pintype "bidirectional"))
      (node (ref "X2") (pin "3") (pinfunction "2_3") (pintype "passive"))
    )
    (net (code "51") (name "VBUS") (class "Default")
      (node (ref "C1") (pin "1") (pinfunction "1_1") (pintype "passive"))
      (node (ref "C3") (pin "1") (pinfunction "1_1") (pintype "passive"))
      (node (ref "C7") (pin "1") (pinfunction "1_1") (pintype "passive"))
      (node (ref "J1") (pin "5") (pinfunction "5_5") (pintype "passive"))
      (node (ref "J1") (pin "6") (pinfunction "6_6") (pintype "passive"))
      (node (ref "J1") (pin "7") (pinfunction "7_7") (pintype "passive"))
      (node (ref "J1") (pin "8") (pinfunction "8_8") (pintype "passive"))
      (node (ref "J3") (pin "5") (pinfunction "5_5") (pintype "passive"))
      (node (ref "J3") (pin "6") (pinfunction "6_6") (pintype "passive"))
      (node (ref "J4") (pin "5") (pinfunction "5_5") (pintype "passive"))
      (node (ref "J4") (pin "6") (pinfunction "6_6") (pintype "passive"))
      (node (ref "J5") (pin "5") (pinfunction "5_5") (pintype "passive"))
      (node (ref "J5") (pin "6") (pinfunction "6_6") (pintype "passive"))
      (node (ref "J6") (pin "5") (pinfunction "5_5") (pintype "passive"))
      (node (ref "J6") (pin "6") (pinfunction "6_6") (pintype "passive"))
      (node (ref "JP9") (pin "3") (pinfunction "3_3") (pintype "passive"))
      (node (ref "JP9") (pin "4") (pinfunction "4_4") (pintype "passive"))
      (node (ref "R1") (pin "2") (pinfunction "2_2") (pintype "passive"))
      (node (ref "U2") (pin "12-13") (pinfunction "VIN_12-13") (pintype "power_in"))
    )
    (net (code "52") (name "unconnected-(J8-NC{slash}TDI-Pad8)") (class "Default")
      (node (ref "J8") (pin "8") (pinfunction "NC/TDI_8") (pintype "passive"))
    )
    (net (code "53") (name "unconnected-(J8-SWO{slash}TDO-Pad6)") (class "Default")
      (node (ref "J8") (pin "6") (pinfunction "SWO/TDO_6") (pintype "passive"))
    )
  )
)
